# McPiFace-Environment-V2.net
KiCad netlist of a schematic drawn in EAGLE
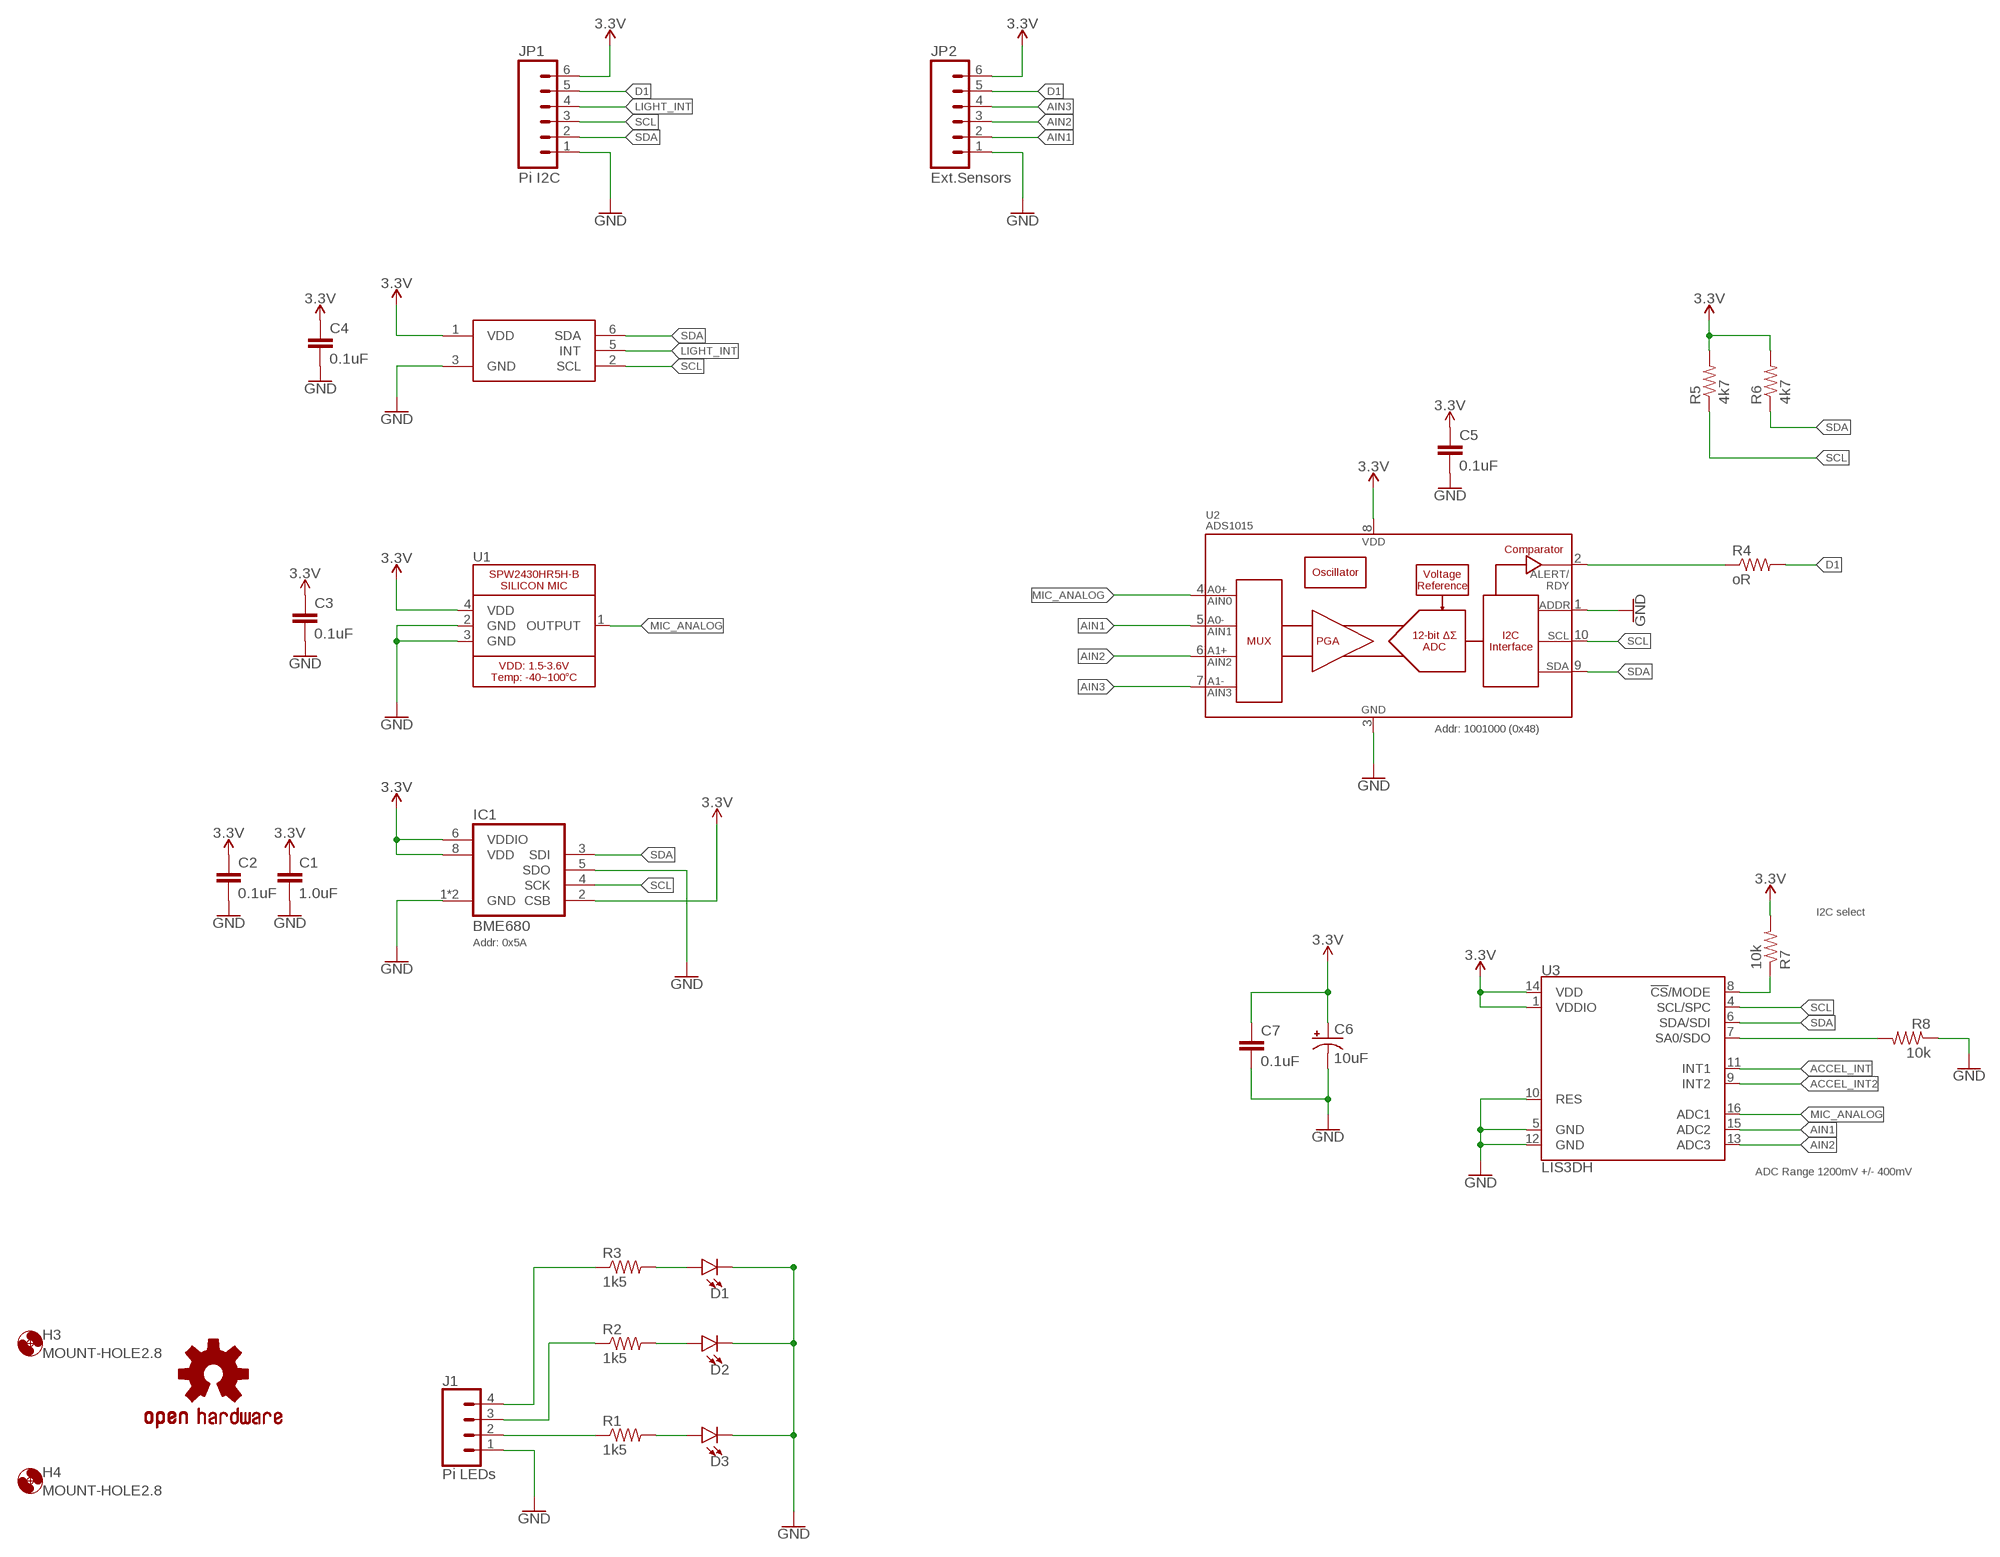
[diagram p0: schematic, sheet 1]

(export (version "E")
  (design (tool "Eeschema 10.0.6"))
  (components
    (comp (ref "C1")
      (value "1.0uF")
      (footprint "eagle-import:0805")
      (libsource (lib "eagle-import") (part "CAP0805"))
    )
    (comp (ref "C2")
      (value "0.1uF")
      (footprint "eagle-import:0805")
      (libsource (lib "eagle-import") (part "CAP0805"))
    )
    (comp (ref "C3")
      (value "0.1uF")
      (footprint "eagle-import:0805")
      (libsource (lib "eagle-import") (part "CAP0805"))
    )
    (comp (ref "C4")
      (value "0.1uF")
      (footprint "eagle-import:0805")
      (libsource (lib "eagle-import") (part "CAP0805"))
    )
    (comp (ref "C5")
      (value "0.1uF")
      (footprint "eagle-import:0805")
      (libsource (lib "eagle-import") (part "CAP0805"))
    )
    (comp (ref "C6")
      (value "10uF")
      (footprint "eagle-import:EIA3216")
      (libsource (lib "eagle-import") (part "10UF-16V-10%(TANT)"))
    )
    (comp (ref "C7")
      (value "0.1uF")
      (footprint "eagle-import:0805")
      (libsource (lib "eagle-import") (part "CAP0805"))
    )
    (comp (ref "D1")
      (value "LED1206-BOTTOM-1.6MM")
      (footprint "eagle-import:LED-1206-BOTTOM-1.6MM")
      (libsource (lib "eagle-import") (part "LED1206-BOTTOM-1.6MM"))
    )
    (comp (ref "D2")
      (value "LED1206-BOTTOM-1.6MM")
      (footprint "eagle-import:LED-1206-BOTTOM-1.6MM")
      (libsource (lib "eagle-import") (part "LED1206-BOTTOM-1.6MM"))
    )
    (comp (ref "D3")
      (value "LED1206-BOTTOM-1.6MM")
      (footprint "eagle-import:LED-1206-BOTTOM-1.6MM")
      (libsource (lib "eagle-import") (part "LED1206-BOTTOM-1.6MM"))
    )
    (comp (ref "H3")
      (value "MOUNT-HOLE2.8")
      (footprint "eagle-import:2,8")
      (libsource (lib "eagle-import") (part "MOUNT-HOLE2.8"))
    )
    (comp (ref "H4")
      (value "MOUNT-HOLE2.8")
      (footprint "eagle-import:2,8")
      (libsource (lib "eagle-import") (part "MOUNT-HOLE2.8"))
    )
    (comp (ref "IC1")
      (value "BME680")
      (footprint "eagle-import:BME680")
      (libsource (lib "eagle-import") (part "BME680"))
    )
    (comp (ref "J1")
      (value "Pi LEDs")
      (footprint "eagle-import:1X04_1MM_RA")
      (libsource (lib "eagle-import") (part "CONN_04SMD2"))
    )
    (comp (ref "JP1")
      (value "Pi I2C")
      (footprint "eagle-import:1X06-1MM")
      (libsource (lib "eagle-import") (part "M06SMD-1MM"))
    )
    (comp (ref "JP2")
      (value "Ext.Sensors")
      (footprint "eagle-import:1X06-1MM")
      (libsource (lib "eagle-import") (part "M06SMD-1MM"))
    )
    (comp (ref "LOGO1")
      (value "OSHW-LOGOL")
      (footprint "eagle-import:OSHW-LOGO-L")
      (libsource (lib "eagle-import") (part "OSHW-LOGOL"))
    )
    (comp (ref "R1")
      (value "1k5")
      (footprint "eagle-import:0805")
      (libsource (lib "eagle-import") (part "RESISTOR0805-RES"))
    )
    (comp (ref "R2")
      (value "1k5")
      (footprint "eagle-import:0805")
      (libsource (lib "eagle-import") (part "RESISTOR0805-RES"))
    )
    (comp (ref "R3")
      (value "1k5")
      (footprint "eagle-import:0805")
      (libsource (lib "eagle-import") (part "RESISTOR0805-RES"))
    )
    (comp (ref "R4")
      (value "oR")
      (footprint "eagle-import:0805")
      (libsource (lib "eagle-import") (part "RESISTOR0805-RES"))
    )
    (comp (ref "R5")
      (value "4k7")
      (footprint "eagle-import:0805")
      (libsource (lib "eagle-import") (part "RESISTOR0805-RES"))
    )
    (comp (ref "R6")
      (value "4k7")
      (footprint "eagle-import:0805")
      (libsource (lib "eagle-import") (part "RESISTOR0805-RES"))
    )
    (comp (ref "R7")
      (value "10k")
      (footprint "eagle-import:0805")
      (libsource (lib "eagle-import") (part "RESISTOR0805-RES"))
    )
    (comp (ref "R8")
      (value "10k")
      (footprint "eagle-import:0805")
      (libsource (lib "eagle-import") (part "RESISTOR0805-RES"))
    )
    (comp (ref "U$1")
      (value "TCS3472")
      (footprint "eagle-import:FN-6")
      (libsource (lib "eagle-import") (part "TCS3472"))
    )
    (comp (ref "U1")
      (value "SPW2430HR5H-B")
      (footprint "eagle-import:SPW2430HR5H-B")
      (libsource (lib "eagle-import") (part "SPW2430HR5H-B"))
    )
    (comp (ref "U2")
      (value "ADS1015")
      (footprint "eagle-import:MSOP10")
      (libsource (lib "eagle-import") (part "ADS1015"))
    )
    (comp (ref "U3")
      (value "LIS3DH")
      (footprint "eagle-import:LGA-16-3X3")
      (libsource (lib "eagle-import") (part "LIS3DH"))
    )
  )
  (nets
    (net (code "1") (name "3.3V") (class "Default")
      (node (ref "C1") (pin "1") (pinfunction "1_1") (pintype "passive"))
      (node (ref "C2") (pin "1") (pinfunction "1_1") (pintype "passive"))
      (node (ref "C3") (pin "1") (pinfunction "1_1") (pintype "passive"))
      (node (ref "C4") (pin "1") (pinfunction "1_1") (pintype "passive"))
      (node (ref "C5") (pin "1") (pinfunction "1_1") (pintype "passive"))
      (node (ref "C6") (pin "A") (pinfunction "+_A") (pintype "passive"))
      (node (ref "C7") (pin "1") (pinfunction "1_1") (pintype "passive"))
      (node (ref "IC1") (pin "2") (pinfunction "CSB_2") (pintype "input"))
      (node (ref "IC1") (pin "6") (pinfunction "VDDIO_6") (pintype "power_in"))
      (node (ref "IC1") (pin "8") (pinfunction "VDD_8") (pintype "power_in"))
      (node (ref "JP1") (pin "6") (pinfunction "6_6") (pintype "passive"))
      (node (ref "JP2") (pin "6") (pinfunction "6_6") (pintype "passive"))
      (node (ref "R5") (pin "2") (pinfunction "2_2") (pintype "passive"))
      (node (ref "R6") (pin "2") (pinfunction "2_2") (pintype "passive"))
      (node (ref "R7") (pin "2") (pinfunction "2_2") (pintype "passive"))
      (node (ref "U$1") (pin "1") (pinfunction "VDD_1") (pintype "bidirectional"))
      (node (ref "U1") (pin "4") (pinfunction "VDD_4") (pintype "power_in"))
      (node (ref "U2") (pin "8") (pinfunction "VDD_8") (pintype "bidirectional"))
      (node (ref "U3") (pin "1") (pinfunction "VDDIO_1") (pintype "bidirectional"))
      (node (ref "U3") (pin "14") (pinfunction "VDD_14") (pintype "bidirectional"))
    )
    (net (code "2") (name "ACCEL_INT") (class "Default")
      (node (ref "U3") (pin "11") (pinfunction "INT1_11") (pintype "bidirectional"))
    )
    (net (code "3") (name "ACCEL_INT2") (class "Default")
      (node (ref "U3") (pin "9") (pinfunction "INT2_9") (pintype "bidirectional"))
    )
    (net (code "4") (name "AIN1") (class "Default")
      (node (ref "JP2") (pin "2") (pinfunction "2_2") (pintype "passive"))
      (node (ref "U2") (pin "5") (pinfunction "AIN1_5") (pintype "bidirectional"))
      (node (ref "U3") (pin "15") (pinfunction "ADC2_15") (pintype "bidirectional"))
    )
    (net (code "5") (name "AIN2") (class "Default")
      (node (ref "JP2") (pin "3") (pinfunction "3_3") (pintype "passive"))
      (node (ref "U2") (pin "6") (pinfunction "AIN2_6") (pintype "bidirectional"))
      (node (ref "U3") (pin "13") (pinfunction "ADC3_13") (pintype "bidirectional"))
    )
    (net (code "6") (name "AIN3") (class "Default")
      (node (ref "JP2") (pin "4") (pinfunction "4_4") (pintype "passive"))
      (node (ref "U2") (pin "7") (pinfunction "AIN3_7") (pintype "bidirectional"))
    )
    (net (code "7") (name "D1") (class "Default")
      (node (ref "JP1") (pin "5") (pinfunction "5_5") (pintype "passive"))
      (node (ref "JP2") (pin "5") (pinfunction "5_5") (pintype "passive"))
      (node (ref "R4") (pin "2") (pinfunction "2_2") (pintype "passive"))
    )
    (net (code "8") (name "GND") (class "Default")
      (node (ref "C1") (pin "2") (pinfunction "2_2") (pintype "passive"))
      (node (ref "C2") (pin "2") (pinfunction "2_2") (pintype "passive"))
      (node (ref "C3") (pin "2") (pinfunction "2_2") (pintype "passive"))
      (node (ref "C4") (pin "2") (pinfunction "2_2") (pintype "passive"))
      (node (ref "C5") (pin "2") (pinfunction "2_2") (pintype "passive"))
      (node (ref "C6") (pin "C") (pinfunction "-_C") (pintype "passive"))
      (node (ref "C7") (pin "2") (pinfunction "2_2") (pintype "passive"))
      (node (ref "D1") (pin "C") (pinfunction "C_C") (pintype "passive"))
      (node (ref "D2") (pin "C") (pinfunction "C_C") (pintype "passive"))
      (node (ref "D3") (pin "C") (pinfunction "C_C") (pintype "passive"))
      (node (ref "IC1") (pin "1") (pinfunction "GND_1") (pintype "power_in"))
      (node (ref "IC1") (pin "5") (pinfunction "SDO_5") (pintype "output"))
      (node (ref "IC1") (pin "7") (pinfunction "GND_7") (pintype "power_in"))
      (node (ref "J1") (pin "1") (pinfunction "1_1") (pintype "passive"))
      (node (ref "JP1") (pin "1") (pinfunction "1_1") (pintype "passive"))
      (node (ref "JP2") (pin "1") (pinfunction "1_1") (pintype "passive"))
      (node (ref "R8") (pin "1") (pinfunction "1_1") (pintype "passive"))
      (node (ref "U$1") (pin "3") (pinfunction "GND_3") (pintype "bidirectional"))
      (node (ref "U1") (pin "2") (pinfunction "GND_2") (pintype "power_in"))
      (node (ref "U1") (pin "3") (pinfunction "GND_3") (pintype "power_in"))
      (node (ref "U2") (pin "1") (pinfunction "ADDR_1") (pintype "bidirectional"))
      (node (ref "U2") (pin "3") (pinfunction "VSS_3") (pintype "bidirectional"))
      (node (ref "U3") (pin "10") (pinfunction "RES_10") (pintype "bidirectional"))
      (node (ref "U3") (pin "12") (pinfunction "GND_12") (pintype "bidirectional"))
      (node (ref "U3") (pin "5") (pinfunction "GND_5") (pintype "bidirectional"))
    )
    (net (code "9") (name "LIGHT_INT") (class "Default")
      (node (ref "JP1") (pin "4") (pinfunction "4_4") (pintype "passive"))
      (node (ref "U$1") (pin "5") (pinfunction "INT_5") (pintype "bidirectional"))
    )
    (net (code "10") (name "MIC_ANALOG") (class "Default")
      (node (ref "U1") (pin "1") (pinfunction "OUTPUT_1") (pintype "output"))
      (node (ref "U2") (pin "4") (pinfunction "AIN0_4") (pintype "bidirectional"))
      (node (ref "U3") (pin "16") (pinfunction "ADC1_16") (pintype "bidirectional"))
    )
    (net (code "11") (name "Net-(D1-PadA)") (class "Default")
      (node (ref "D1") (pin "A") (pinfunction "A_A") (pintype "passive"))
      (node (ref "R3") (pin "2") (pinfunction "2_2") (pintype "passive"))
    )
    (net (code "12") (name "Net-(D2-PadA)") (class "Default")
      (node (ref "D2") (pin "A") (pinfunction "A_A") (pintype "passive"))
      (node (ref "R2") (pin "2") (pinfunction "2_2") (pintype "passive"))
    )
    (net (code "13") (name "Net-(D3-PadA)") (class "Default")
      (node (ref "D3") (pin "A") (pinfunction "A_A") (pintype "passive"))
      (node (ref "R1") (pin "2") (pinfunction "2_2") (pintype "passive"))
    )
    (net (code "14") (name "Net-(J1-Pad2)") (class "Default")
      (node (ref "J1") (pin "2") (pinfunction "2_2") (pintype "passive"))
      (node (ref "R1") (pin "1") (pinfunction "1_1") (pintype "passive"))
    )
    (net (code "15") (name "Net-(J1-Pad3)") (class "Default")
      (node (ref "J1") (pin "3") (pinfunction "3_3") (pintype "passive"))
      (node (ref "R2") (pin "1") (pinfunction "1_1") (pintype "passive"))
    )
    (net (code "16") (name "Net-(J1-Pad4)") (class "Default")
      (node (ref "J1") (pin "4") (pinfunction "4_4") (pintype "passive"))
      (node (ref "R3") (pin "1") (pinfunction "1_1") (pintype "passive"))
    )
    (net (code "17") (name "Net-(U2-ALERT{slash}RDY)") (class "Default")
      (node (ref "R4") (pin "1") (pinfunction "1_1") (pintype "passive"))
      (node (ref "U2") (pin "2") (pinfunction "ALERT/RDY_2") (pintype "bidirectional"))
    )
    (net (code "18") (name "Net-(U3-SA0{slash}SDO)") (class "Default")
      (node (ref "R8") (pin "2") (pinfunction "2_2") (pintype "passive"))
      (node (ref "U3") (pin "7") (pinfunction "SA0/SDO_7") (pintype "bidirectional"))
    )
    (net (code "19") (name "Net-(U3-~{CS}{slash}MODE)") (class "Default")
      (node (ref "R7") (pin "1") (pinfunction "1_1") (pintype "passive"))
      (node (ref "U3") (pin "8") (pinfunction "~{CS}/MODE_8") (pintype "bidirectional"))
    )
    (net (code "20") (name "SCL") (class "Default")
      (node (ref "IC1") (pin "4") (pinfunction "SCK_4") (pintype "input"))
      (node (ref "JP1") (pin "3") (pinfunction "3_3") (pintype "passive"))
      (node (ref "R5") (pin "1") (pinfunction "1_1") (pintype "passive"))
      (node (ref "U$1") (pin "2") (pinfunction "SCL_2") (pintype "bidirectional"))
      (node (ref "U2") (pin "10") (pinfunction "SCL_10") (pintype "bidirectional"))
      (node (ref "U3") (pin "4") (pinfunction "SCL/SPC_4") (pintype "bidirectional"))
    )
    (net (code "21") (name "SDA") (class "Default")
      (node (ref "IC1") (pin "3") (pinfunction "SDI_3") (pintype "input"))
      (node (ref "JP1") (pin "2") (pinfunction "2_2") (pintype "passive"))
      (node (ref "R6") (pin "1") (pinfunction "1_1") (pintype "passive"))
      (node (ref "U$1") (pin "6") (pinfunction "SDA_6") (pintype "bidirectional"))
      (node (ref "U2") (pin "9") (pinfunction "SDA_9") (pintype "bidirectional"))
      (node (ref "U3") (pin "6") (pinfunction "SDA/SDI_6") (pintype "bidirectional"))
    )
  )
)
